# ESP32.net
KiCad netlist of a schematic drawn in Altium Designer
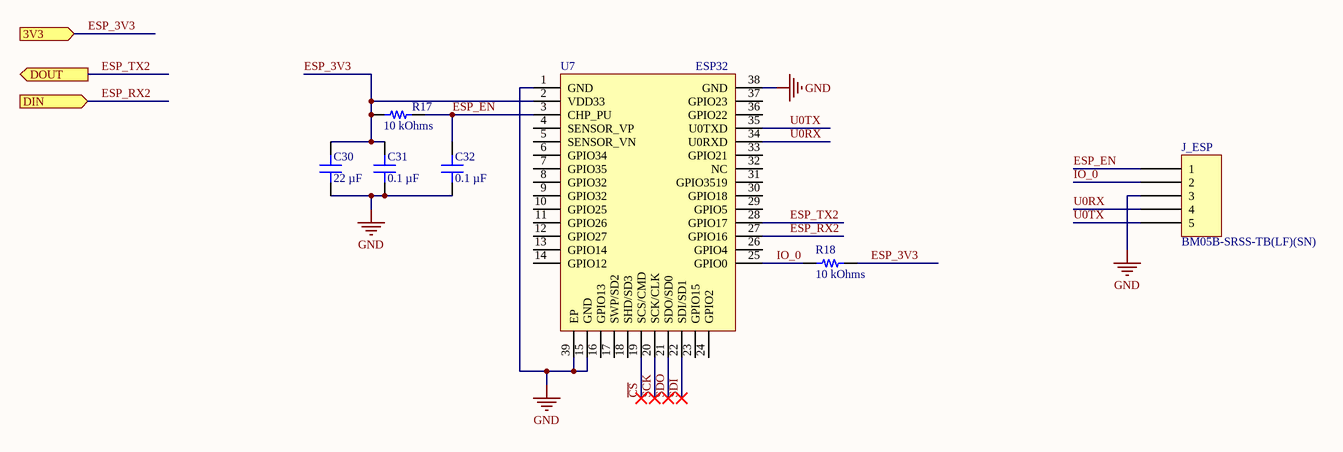
[diagram p0: ESP32.SchDoc]

(export (version "E")
  (design (tool "Eeschema 10.0.6"))
  (components
    (comp (ref "C30")
      (value "22 µF")
      (footprint "CAP 0603_1608")
      (description "CAP CER 47UF 6.3V X5R 0603")
      (fields
        (field (name "PART NUMBER") "C0603B476M007T")
        (field (name "MANUFACTURER") "Holy Stone Enterprise Co., Ltd.")
      )
      (libsource (lib "Celestial Altium Library - altium_library") (part "Capacitor"))
    )
    (comp (ref "C31")
      (value "0.1 µF")
      (footprint "CAP 0402_1005")
      (description "CAP CER 0.1UF 25V X5R 0402")
      (fields
        (field (name "PART NUMBER") "C1005X5R1E104K050BC")
        (field (name "MANUFACTURER") "TDK Corporation")
      )
      (libsource (lib "Celestial Altium Library - altium_library") (part "Capacitor"))
    )
    (comp (ref "C32")
      (value "0.1 µF")
      (footprint "CAP 0402_1005")
      (description "CAP CER 0.1UF 25V X5R 0402")
      (fields
        (field (name "PART NUMBER") "C1005X5R1E104K050BC")
        (field (name "MANUFACTURER") "TDK Corporation")
      )
      (libsource (lib "Celestial Altium Library - altium_library") (part "Capacitor"))
    )
    (comp (ref "J_ESP")
      (value "BM05B-SRSS-TB(LF)(SN)")
      (footprint "JST BM05B-SRSS-TB")
      (description "CONN HEADER SMD 5POS 1MM")
      (fields (field (name "MANUFACTURER") "JST Sales America Inc."))
      (libsource (lib "Celestial Altium Library - altium_library") (part "5 Pin"))
    )
    (comp (ref "R17")
      (value "10 kOhms")
      (footprint "RES 0402_1005")
      (description "RES SMD 10K OHM 0.5% 1/16W 0402")
      (fields (field (name "PART NUMBER") "CRCW040210K0DHEDP") (field (name "MANUFACTURER") "Vishay Dale"))
      (libsource (lib "Celestial Altium Library - altium_library") (part "Resistor"))
    )
    (comp (ref "R18")
      (value "10 kOhms")
      (footprint "RES 0402_1005")
      (description "RES SMD 10K OHM 0.5% 1/16W 0402")
      (fields (field (name "PART NUMBER") "CRCW040210K0DHEDP") (field (name "MANUFACTURER") "Vishay Dale"))
      (libsource (lib "Celestial Altium Library - altium_library") (part "Resistor"))
    )
    (comp (ref "U7")
      (value "ESP32")
      (footprint "Espressif ESP32-WROOM-32")
      (libsource (lib "IC") (part "ESP32"))
    )
  )
  (nets
    (net (code "1") (name "/ESP_3V3") (class "Default")
      (node (ref "C30") (pin "2") (pinfunction "2_2") (pintype "passive"))
      (node (ref "C31") (pin "2") (pinfunction "2_2") (pintype "passive"))
      (node (ref "R17") (pin "1") (pinfunction "1_1") (pintype "passive"))
      (node (ref "R18") (pin "2") (pinfunction "2_2") (pintype "passive"))
      (node (ref "U7") (pin "2") (pinfunction "VDD33_2") (pintype "passive"))
    )
    (net (code "2") (name "/ESP_EN") (class "Default")
      (node (ref "C32") (pin "2") (pinfunction "2_2") (pintype "passive"))
      (node (ref "J_ESP") (pin "1") (pinfunction "1_1") (pintype "passive"))
      (node (ref "R17") (pin "2") (pinfunction "2_2") (pintype "passive"))
      (node (ref "U7") (pin "3") (pinfunction "CHP_PU_3") (pintype "passive"))
    )
    (net (code "3") (name "/ESP_RX2") (class "Default")
      (node (ref "U7") (pin "27") (pinfunction "GPIO16_27") (pintype "passive"))
    )
    (net (code "4") (name "/ESP_TX2") (class "Default")
      (node (ref "U7") (pin "28") (pinfunction "GPIO17_28") (pintype "passive"))
    )
    (net (code "5") (name "/IO_0") (class "Default")
      (node (ref "J_ESP") (pin "2") (pinfunction "2_2") (pintype "passive"))
      (node (ref "R18") (pin "1") (pinfunction "1_1") (pintype "passive"))
      (node (ref "U7") (pin "25") (pinfunction "GPIO0_25") (pintype "passive"))
    )
    (net (code "6") (name "/SCK") (class "Default")
      (node (ref "U7") (pin "20") (pinfunction "SCK/CLK_20") (pintype "passive+no_connect"))
    )
    (net (code "7") (name "/SDI") (class "Default")
      (node (ref "U7") (pin "22") (pinfunction "SDI/SD1_22") (pintype "passive+no_connect"))
    )
    (net (code "8") (name "/SDO") (class "Default")
      (node (ref "U7") (pin "21") (pinfunction "SDO/SD0_21") (pintype "passive+no_connect"))
    )
    (net (code "9") (name "/U0RX") (class "Default")
      (node (ref "J_ESP") (pin "4") (pinfunction "4_4") (pintype "passive"))
      (node (ref "U7") (pin "34") (pinfunction "U0RXD_34") (pintype "passive"))
    )
    (net (code "10") (name "/U0TX") (class "Default")
      (node (ref "J_ESP") (pin "5") (pinfunction "5_5") (pintype "passive"))
      (node (ref "U7") (pin "35") (pinfunction "U0TXD_35") (pintype "passive"))
    )
    (net (code "11") (name "/~{CS}") (class "Default")
      (node (ref "U7") (pin "19") (pinfunction "SCS/CMD_19") (pintype "passive+no_connect"))
    )
    (net (code "12") (name "GND") (class "Default")
      (node (ref "C30") (pin "1") (pinfunction "1_1") (pintype "passive"))
      (node (ref "C31") (pin "1") (pinfunction "1_1") (pintype "passive"))
      (node (ref "C32") (pin "1") (pinfunction "1_1") (pintype "passive"))
      (node (ref "J_ESP") (pin "3") (pinfunction "3_3") (pintype "passive"))
      (node (ref "U7") (pin "1") (pinfunction "GND_1") (pintype "passive"))
      (node (ref "U7") (pin "15") (pinfunction "GND_15") (pintype "passive"))
      (node (ref "U7") (pin "38") (pinfunction "GND_38") (pintype "passive"))
      (node (ref "U7") (pin "39") (pinfunction "EP_39") (pintype "passive"))
    )
    (net (code "13") (name "unconnected-(U7-GPIO2-Pad24)") (class "Default")
      (node (ref "U7") (pin "24") (pinfunction "GPIO2_24") (pintype "passive"))
    )
    (net (code "14") (name "unconnected-(U7-GPIO4-Pad26)") (class "Default")
      (node (ref "U7") (pin "26") (pinfunction "GPIO4_26") (pintype "passive"))
    )
    (net (code "15") (name "unconnected-(U7-GPIO5-Pad29)") (class "Default")
      (node (ref "U7") (pin "29") (pinfunction "GPIO5_29") (pintype "passive"))
    )
    (net (code "16") (name "unconnected-(U7-GPIO12-Pad14)") (class "Default")
      (node (ref "U7") (pin "14") (pinfunction "GPIO12_14") (pintype "passive"))
    )
    (net (code "17") (name "unconnected-(U7-GPIO13-Pad16)") (class "Default")
      (node (ref "U7") (pin "16") (pinfunction "GPIO13_16") (pintype "passive"))
    )
    (net (code "18") (name "unconnected-(U7-GPIO14-Pad13)") (class "Default")
      (node (ref "U7") (pin "13") (pinfunction "GPIO14_13") (pintype "passive"))
    )
    (net (code "19") (name "unconnected-(U7-GPIO15-Pad23)") (class "Default")
      (node (ref "U7") (pin "23") (pinfunction "GPIO15_23") (pintype "passive"))
    )
    (net (code "20") (name "unconnected-(U7-GPIO18-Pad30)") (class "Default")
      (node (ref "U7") (pin "30") (pinfunction "GPIO18_30") (pintype "passive"))
    )
    (net (code "21") (name "unconnected-(U7-GPIO21-Pad33)") (class "Default")
      (node (ref "U7") (pin "33") (pinfunction "GPIO21_33") (pintype "passive"))
    )
    (net (code "22") (name "unconnected-(U7-GPIO22-Pad36)") (class "Default")
      (node (ref "U7") (pin "36") (pinfunction "GPIO22_36") (pintype "passive"))
    )
    (net (code "23") (name "unconnected-(U7-GPIO23-Pad37)") (class "Default")
      (node (ref "U7") (pin "37") (pinfunction "GPIO23_37") (pintype "passive"))
    )
    (net (code "24") (name "unconnected-(U7-GPIO25-Pad10)") (class "Default")
      (node (ref "U7") (pin "10") (pinfunction "GPIO25_10") (pintype "passive"))
    )
    (net (code "25") (name "unconnected-(U7-GPIO26-Pad11)") (class "Default")
      (node (ref "U7") (pin "11") (pinfunction "GPIO26_11") (pintype "passive"))
    )
    (net (code "26") (name "unconnected-(U7-GPIO27-Pad12)") (class "Default")
      (node (ref "U7") (pin "12") (pinfunction "GPIO27_12") (pintype "passive"))
    )
    (net (code "27") (name "unconnected-(U7-GPIO32-Pad8)") (class "Default")
      (node (ref "U7") (pin "8") (pinfunction "GPIO32_8") (pintype "passive"))
    )
    (net (code "28") (name "unconnected-(U7-GPIO32-Pad9)") (class "Default")
      (node (ref "U7") (pin "9") (pinfunction "GPIO32_9") (pintype "passive"))
    )
    (net (code "29") (name "unconnected-(U7-GPIO34-Pad6)") (class "Default")
      (node (ref "U7") (pin "6") (pinfunction "GPIO34_6") (pintype "passive"))
    )
    (net (code "30") (name "unconnected-(U7-GPIO35-Pad7)") (class "Default")
      (node (ref "U7") (pin "7") (pinfunction "GPIO35_7") (pintype "passive"))
    )
    (net (code "31") (name "unconnected-(U7-GPIO3519-Pad31)") (class "Default")
      (node (ref "U7") (pin "31") (pinfunction "GPIO3519_31") (pintype "passive"))
    )
    (net (code "32") (name "unconnected-(U7-NC-Pad32)") (class "Default")
      (node (ref "U7") (pin "32") (pinfunction "NC_32") (pintype "passive"))
    )
    (net (code "33") (name "unconnected-(U7-SENSOR_VN-Pad5)") (class "Default")
      (node (ref "U7") (pin "5") (pinfunction "SENSOR_VN_5") (pintype "passive"))
    )
    (net (code "34") (name "unconnected-(U7-SENSOR_VP-Pad4)") (class "Default")
      (node (ref "U7") (pin "4") (pinfunction "SENSOR_VP_4") (pintype "passive"))
    )
    (net (code "35") (name "unconnected-(U7-SHD{slash}SD3-Pad18)") (class "Default")
      (node (ref "U7") (pin "18") (pinfunction "SHD/SD3_18") (pintype "passive"))
    )
    (net (code "36") (name "unconnected-(U7-SWP{slash}SD2-Pad17)") (class "Default")
      (node (ref "U7") (pin "17") (pinfunction "SWP/SD2_17") (pintype "passive"))
    )
  )
)
